# LTC_6811-1.net
KiCad netlist of a schematic drawn in Altium Designer
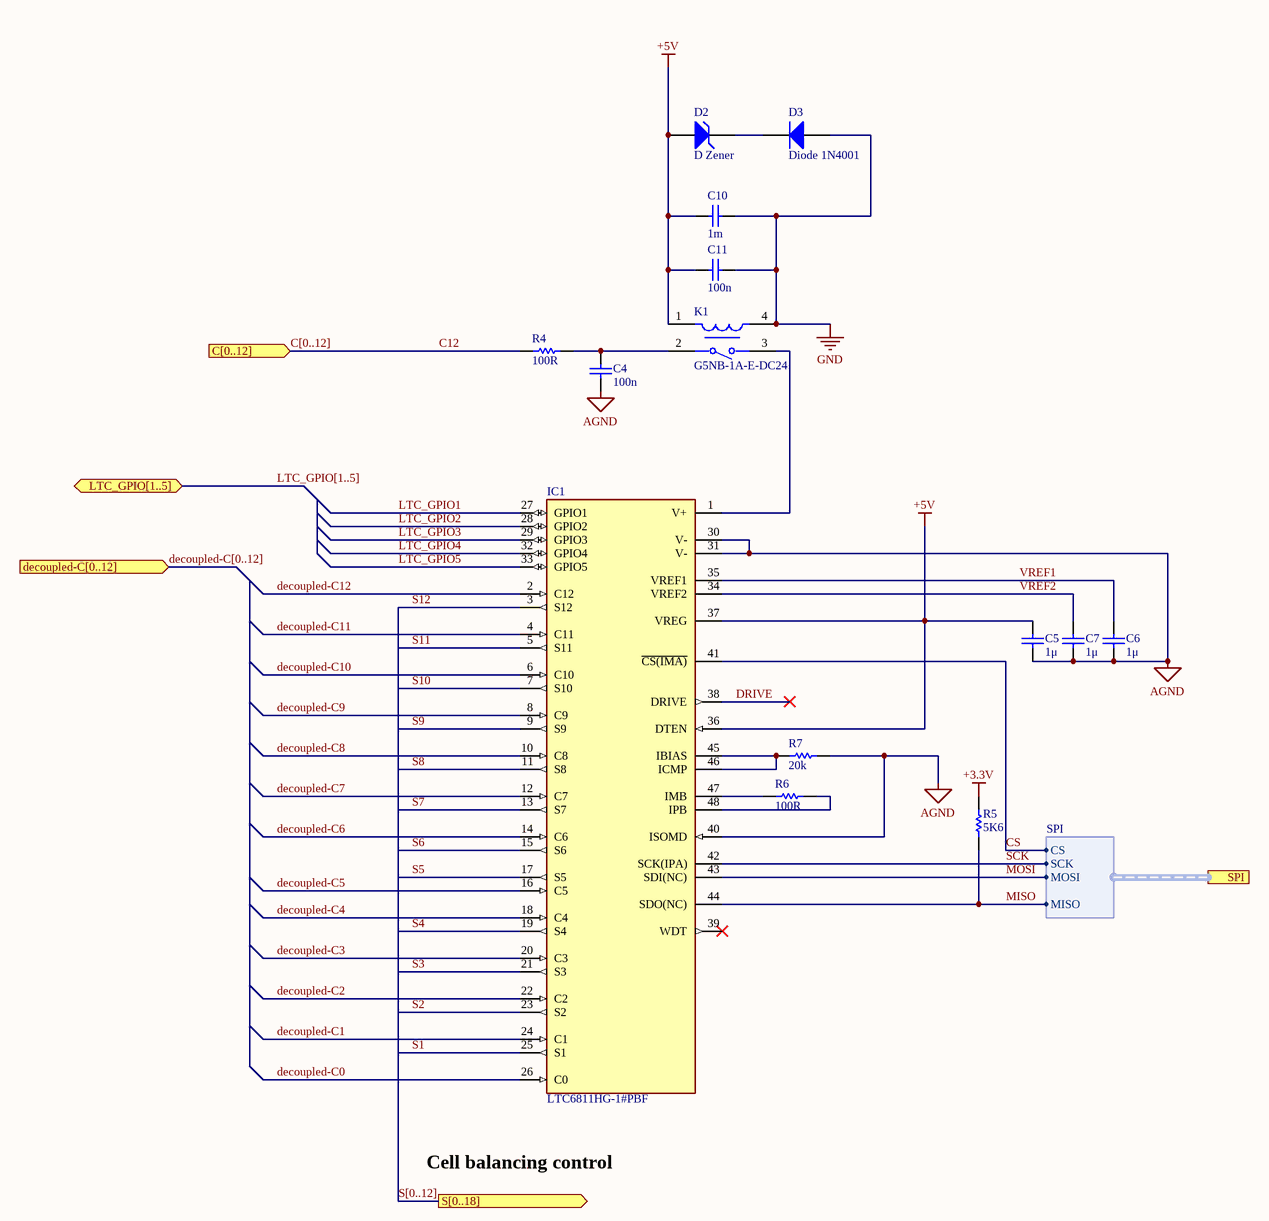
[diagram p0: LTC_6811-1.SchDoc]

(export (version "E")
  (design (tool "Eeschema 10.0.6"))
  (components
    (comp (ref "C4")
      (value "100n")
      (footprint "CAPC0603(1608)55_N")
      (description "Keramikvielschichtkondensator, SMD, Baureihe MC, ± 10%")
      (fields (field (name "MANUFACTURER") "TDK") (field (name "TOLERANCE") "± 10%"))
      (libsource (lib "Res&Caps") (part "Cap 100n"))
    )
    (comp (ref "C5")
      (value "1μ")
      (footprint "CAPC0603(1608)55_N")
      (description "Keramikvielschichtkondensator, SMD, Baureihe MC, ± 10%")
      (fields (field (name "MANUFACTURER") "TDK") (field (name "TOLERANCE") "± 10%"))
      (libsource (lib "Res&Caps") (part "Cap 1μ"))
    )
    (comp (ref "C6")
      (value "1μ")
      (footprint "CAPC0603(1608)55_N")
      (description "Keramikvielschichtkondensator, SMD, Baureihe MC, ± 10%")
      (fields (field (name "MANUFACTURER") "TDK") (field (name "TOLERANCE") "± 10%"))
      (libsource (lib "Res&Caps") (part "Cap 1μ"))
    )
    (comp (ref "C7")
      (value "1μ")
      (footprint "CAPC0603(1608)55_N")
      (description "Keramikvielschichtkondensator, SMD, Baureihe MC, ± 10%")
      (fields (field (name "MANUFACTURER") "TDK") (field (name "TOLERANCE") "± 10%"))
      (libsource (lib "Res&Caps") (part "Cap 1μ"))
    )
    (comp (ref "C10")
      (value "1m")
      (footprint "CAPC0603(1608)55_N")
      (description "Keramikvielschichtkondensator, SMD, Baureihe MC, ± 10%")
      (fields (field (name "MANUFACTURER") "eintragen !!!") (field (name "TOLERANCE") "± eintragen !!!"))
      (libsource (lib "Res&Caps") (part "Cap - template 0603"))
    )
    (comp (ref "C11")
      (value "100n")
      (footprint "CAPC0603(1608)55_N")
      (description "Keramikvielschichtkondensator, SMD, Baureihe MC, ± 10%")
      (fields (field (name "MANUFACTURER") "TDK") (field (name "TOLERANCE") "± 10%"))
      (libsource (lib "Res&Caps") (part "Cap 100n"))
    )
    (comp (ref "D2")
      (value "D Zener")
      (footprint "DIODE-0.7")
      (description "Zener Diode")
      (fields (field (name "PUBLISHER") "Altium Limited"))
      (libsource (lib "Miscellaneous Devices") (part "D Zener"))
    )
    (comp (ref "D3")
      (value "Diode 1N4001")
      (footprint "DO-41")
      (description "1 Amp General Purpose Rectifier")
      (fields (field (name "PUBLISHER") "Altium Limited"))
      (libsource (lib "Miscellaneous Devices") (part "Diode 1N4001"))
    )
    (comp (ref "IC1")
      (value "LTC6811HG-1#PBF")
      (footprint "FP-G-48-05-08-1887-MFG")
      (description "IC MONITOR BATT STACK 48SSOP")
      (fields
        (field (name "OCTOPART") "https://octopart.com/ltc6811hg-1%23pbf-analog+devices-88968888")
        (field (name "MANUFACTURER") "Analog Devices")
      )
      (libsource (lib "Altium Content Vault") (part "6f454705386c9b48cfe577abcc37586"))
    )
    (comp (ref "K1")
      (value "G5NB-1A-E-DC24")
      (footprint "FP-G5NB-1A-E-DC24-MFG")
      (description "RELAY GEN PURPOSE SPST 5A 24V")
      (libsource (lib "Altium Content Vault") (part "9418f1969653264de2d8427a6ca49c6"))
    )
    (comp (ref "R4")
      (value "100R")
      (footprint "RESC0603(1608)_N")
      (description "Chipwiderstand, SMD, Baureihe MC, 1%")
      (fields (field (name "MANUFACTURER") "Multicomp") (field (name "POWER") "100mW"))
      (libsource (lib "Res&Caps") (part "Res 100R"))
    )
    (comp (ref "R5")
      (value "5K6")
      (footprint "RESC0603(1608)_N")
      (description "Chipwiderstand, SMD, Baureihe MC, 1%")
      (fields (field (name "MANUFACTURER") "Multicomp") (field (name "POWER") "100mW"))
      (libsource (lib "Res&Caps") (part "Res 5K6"))
    )
    (comp (ref "R6")
      (value "100R")
      (footprint "RESC0603(1608)_N")
      (description "Chipwiderstand, SMD, Baureihe MC, 1%")
      (fields (field (name "MANUFACTURER") "Multicomp") (field (name "POWER") "100mW"))
      (libsource (lib "Res&Caps") (part "Res 100R"))
    )
    (comp (ref "R7")
      (value "20k")
      (footprint "RESC0603(1608)_N")
      (description "Chipwiderstand, SMD, Baureihe MC, 1%")
      (fields (field (name "MANUFACTURER") "Multicomp") (field (name "POWER") "100mW"))
      (libsource (lib "Res&Caps") (part "Res - template 0603"))
    )
  )
  (nets
    (net (code "15") (name "+3.3V") (class "Default")
      (node (ref "R5") (pin "2") (pinfunction "2_2") (pintype "passive"))
    )
    (net (code "16") (name "+5V") (class "Default")
      (node (ref "C10") (pin "1") (pinfunction "1_1") (pintype "passive"))
      (node (ref "C11") (pin "1") (pinfunction "1_1") (pintype "passive"))
      (node (ref "C5") (pin "2") (pinfunction "2_2") (pintype "passive"))
      (node (ref "D2") (pin "1") (pinfunction "A_1") (pintype "passive"))
      (node (ref "IC1") (pin "36") (pinfunction "DTEN_36") (pintype "input"))
      (node (ref "IC1") (pin "37") (pinfunction "VREG_37") (pintype "power_in"))
      (node (ref "K1") (pin "1") (pinfunction "1_1") (pintype "passive"))
    )
    (net (code "17") (name "/C12") (class "Default")
      (node (ref "R4") (pin "1") (pinfunction "1_1") (pintype "passive"))
    )
    (net (code "18") (name "/CS") (class "Default")
      (node (ref "IC1") (pin "41") (pinfunction "~{CS(IMA)}_41") (pintype "passive"))
    )
    (net (code "20") (name "/DRIVE") (class "Default")
      (node (ref "IC1") (pin "38") (pinfunction "DRIVE_38") (pintype "output+no_connect"))
    )
    (net (code "21") (name "/LTC_GPIO1") (class "Default")
      (node (ref "IC1") (pin "27") (pinfunction "GPIO1_27") (pintype "bidirectional"))
    )
    (net (code "22") (name "/LTC_GPIO2") (class "Default")
      (node (ref "IC1") (pin "28") (pinfunction "GPIO2_28") (pintype "bidirectional"))
    )
    (net (code "23") (name "/LTC_GPIO3") (class "Default")
      (node (ref "IC1") (pin "29") (pinfunction "GPIO3_29") (pintype "bidirectional"))
    )
    (net (code "24") (name "/LTC_GPIO4") (class "Default")
      (node (ref "IC1") (pin "32") (pinfunction "GPIO4_32") (pintype "bidirectional"))
    )
    (net (code "25") (name "/LTC_GPIO5") (class "Default")
      (node (ref "IC1") (pin "33") (pinfunction "GPIO5_33") (pintype "bidirectional"))
    )
    (net (code "27") (name "/MISO") (class "Default")
      (node (ref "IC1") (pin "44") (pinfunction "SDO(NC)_44") (pintype "passive"))
      (node (ref "R5") (pin "1") (pinfunction "1_1") (pintype "passive"))
    )
    (net (code "28") (name "/MOSI") (class "Default")
      (node (ref "IC1") (pin "43") (pinfunction "SDI(NC)_43") (pintype "passive"))
    )
    (net (code "29") (name "/S1") (class "Default")
      (node (ref "IC1") (pin "25") (pinfunction "S1_25") (pintype "output"))
    )
    (net (code "30") (name "/S2") (class "Default")
      (node (ref "IC1") (pin "23") (pinfunction "S2_23") (pintype "output"))
    )
    (net (code "31") (name "/S3") (class "Default")
      (node (ref "IC1") (pin "21") (pinfunction "S3_21") (pintype "output"))
    )
    (net (code "32") (name "/S4") (class "Default")
      (node (ref "IC1") (pin "19") (pinfunction "S4_19") (pintype "output"))
    )
    (net (code "33") (name "/S5") (class "Default")
      (node (ref "IC1") (pin "17") (pinfunction "S5_17") (pintype "output"))
    )
    (net (code "34") (name "/S6") (class "Default")
      (node (ref "IC1") (pin "15") (pinfunction "S6_15") (pintype "output"))
    )
    (net (code "35") (name "/S7") (class "Default")
      (node (ref "IC1") (pin "13") (pinfunction "S7_13") (pintype "output"))
    )
    (net (code "36") (name "/S8") (class "Default")
      (node (ref "IC1") (pin "11") (pinfunction "S8_11") (pintype "output"))
    )
    (net (code "37") (name "/S9") (class "Default")
      (node (ref "IC1") (pin "9") (pinfunction "S9_9") (pintype "output"))
    )
    (net (code "38") (name "/S10") (class "Default")
      (node (ref "IC1") (pin "7") (pinfunction "S10_7") (pintype "output"))
    )
    (net (code "39") (name "/S11") (class "Default")
      (node (ref "IC1") (pin "5") (pinfunction "S11_5") (pintype "output"))
    )
    (net (code "40") (name "/S12") (class "Default")
      (node (ref "IC1") (pin "3") (pinfunction "S12_3") (pintype "output"))
    )
    (net (code "41") (name "/SCK") (class "Default")
      (node (ref "IC1") (pin "42") (pinfunction "SCK(IPA)_42") (pintype "passive"))
    )
    (net (code "43") (name "/VREF1") (class "Default")
      (node (ref "C6") (pin "2") (pinfunction "2_2") (pintype "passive"))
      (node (ref "IC1") (pin "35") (pinfunction "VREF1_35") (pintype "power_in"))
    )
    (net (code "44") (name "/VREF2") (class "Default")
      (node (ref "C7") (pin "2") (pinfunction "2_2") (pintype "passive"))
      (node (ref "IC1") (pin "34") (pinfunction "VREF2_34") (pintype "power_in"))
    )
    (net (code "45") (name "/decoupled-C0") (class "Default")
      (node (ref "IC1") (pin "26") (pinfunction "C0_26") (pintype "input"))
    )
    (net (code "46") (name "/decoupled-C1") (class "Default")
      (node (ref "IC1") (pin "24") (pinfunction "C1_24") (pintype "input"))
    )
    (net (code "47") (name "/decoupled-C2") (class "Default")
      (node (ref "IC1") (pin "22") (pinfunction "C2_22") (pintype "input"))
    )
    (net (code "48") (name "/decoupled-C3") (class "Default")
      (node (ref "IC1") (pin "20") (pinfunction "C3_20") (pintype "input"))
    )
    (net (code "49") (name "/decoupled-C4") (class "Default")
      (node (ref "IC1") (pin "18") (pinfunction "C4_18") (pintype "input"))
    )
    (net (code "50") (name "/decoupled-C5") (class "Default")
      (node (ref "IC1") (pin "16") (pinfunction "C5_16") (pintype "input"))
    )
    (net (code "51") (name "/decoupled-C6") (class "Default")
      (node (ref "IC1") (pin "14") (pinfunction "C6_14") (pintype "input"))
    )
    (net (code "52") (name "/decoupled-C7") (class "Default")
      (node (ref "IC1") (pin "12") (pinfunction "C7_12") (pintype "input"))
    )
    (net (code "53") (name "/decoupled-C8") (class "Default")
      (node (ref "IC1") (pin "10") (pinfunction "C8_10") (pintype "input"))
    )
    (net (code "54") (name "/decoupled-C9") (class "Default")
      (node (ref "IC1") (pin "8") (pinfunction "C9_8") (pintype "input"))
    )
    (net (code "55") (name "/decoupled-C10") (class "Default")
      (node (ref "IC1") (pin "6") (pinfunction "C10_6") (pintype "input"))
    )
    (net (code "56") (name "/decoupled-C11") (class "Default")
      (node (ref "IC1") (pin "4") (pinfunction "C11_4") (pintype "input"))
    )
    (net (code "57") (name "/decoupled-C12") (class "Default")
      (node (ref "IC1") (pin "2") (pinfunction "C12_2") (pintype "input"))
    )
    (net (code "60") (name "AGND") (class "Default")
      (node (ref "C4") (pin "1") (pinfunction "1_1") (pintype "passive"))
      (node (ref "C5") (pin "1") (pinfunction "1_1") (pintype "passive"))
      (node (ref "C6") (pin "1") (pinfunction "1_1") (pintype "passive"))
      (node (ref "C7") (pin "1") (pinfunction "1_1") (pintype "passive"))
      (node (ref "IC1") (pin "30") (pinfunction "V-_30") (pintype "power_in"))
      (node (ref "IC1") (pin "31") (pinfunction "V-_31") (pintype "power_in"))
      (node (ref "IC1") (pin "40") (pinfunction "ISOMD_40") (pintype "input"))
      (node (ref "R7") (pin "2") (pinfunction "2_2") (pintype "passive"))
    )
    (net (code "61") (name "GND") (class "Default")
      (node (ref "C10") (pin "2") (pinfunction "2_2") (pintype "passive"))
      (node (ref "C11") (pin "2") (pinfunction "2_2") (pintype "passive"))
      (node (ref "D3") (pin "1") (pinfunction "A_1") (pintype "passive"))
      (node (ref "K1") (pin "4") (pinfunction "4_4") (pintype "passive"))
    )
    (net (code "62") (name "Net-(C4-Pad2)") (class "Default")
      (node (ref "C4") (pin "2") (pinfunction "2_2") (pintype "passive"))
      (node (ref "K1") (pin "2") (pinfunction "2_2") (pintype "passive"))
      (node (ref "R4") (pin "2") (pinfunction "2_2") (pintype "passive"))
    )
    (net (code "63") (name "Net-(D2-K)") (class "Default")
      (node (ref "D2") (pin "2") (pinfunction "K_2") (pintype "passive"))
      (node (ref "D3") (pin "2") (pinfunction "K_2") (pintype "passive"))
    )
    (net (code "64") (name "Net-(IC1-IBIAS)") (class "Default")
      (node (ref "IC1") (pin "45") (pinfunction "IBIAS_45") (pintype "passive"))
      (node (ref "IC1") (pin "46") (pinfunction "ICMP_46") (pintype "passive"))
      (node (ref "R7") (pin "1") (pinfunction "1_1") (pintype "passive"))
    )
    (net (code "65") (name "Net-(IC1-IMB)") (class "Default")
      (node (ref "IC1") (pin "47") (pinfunction "IMB_47") (pintype "passive"))
      (node (ref "R6") (pin "1") (pinfunction "1_1") (pintype "passive"))
    )
    (net (code "66") (name "Net-(IC1-IPB)") (class "Default")
      (node (ref "IC1") (pin "48") (pinfunction "IPB_48") (pintype "passive"))
      (node (ref "R6") (pin "2") (pinfunction "2_2") (pintype "passive"))
    )
    (net (code "67") (name "Net-(IC1-V+)") (class "Default")
      (node (ref "IC1") (pin "1") (pinfunction "V+_1") (pintype "power_in"))
      (node (ref "K1") (pin "3") (pinfunction "3_3") (pintype "passive"))
    )
    (net (code "68") (name "unconnected-(IC1-WDT-Pad39)") (class "Default")
      (node (ref "IC1") (pin "39") (pinfunction "WDT_39") (pintype "output+no_connect"))
    )
  )
)
